# SCH_Line_Following_Robot_PCB_2023-12-15_.net
KiCad netlist of a schematic drawn in EasyEDA
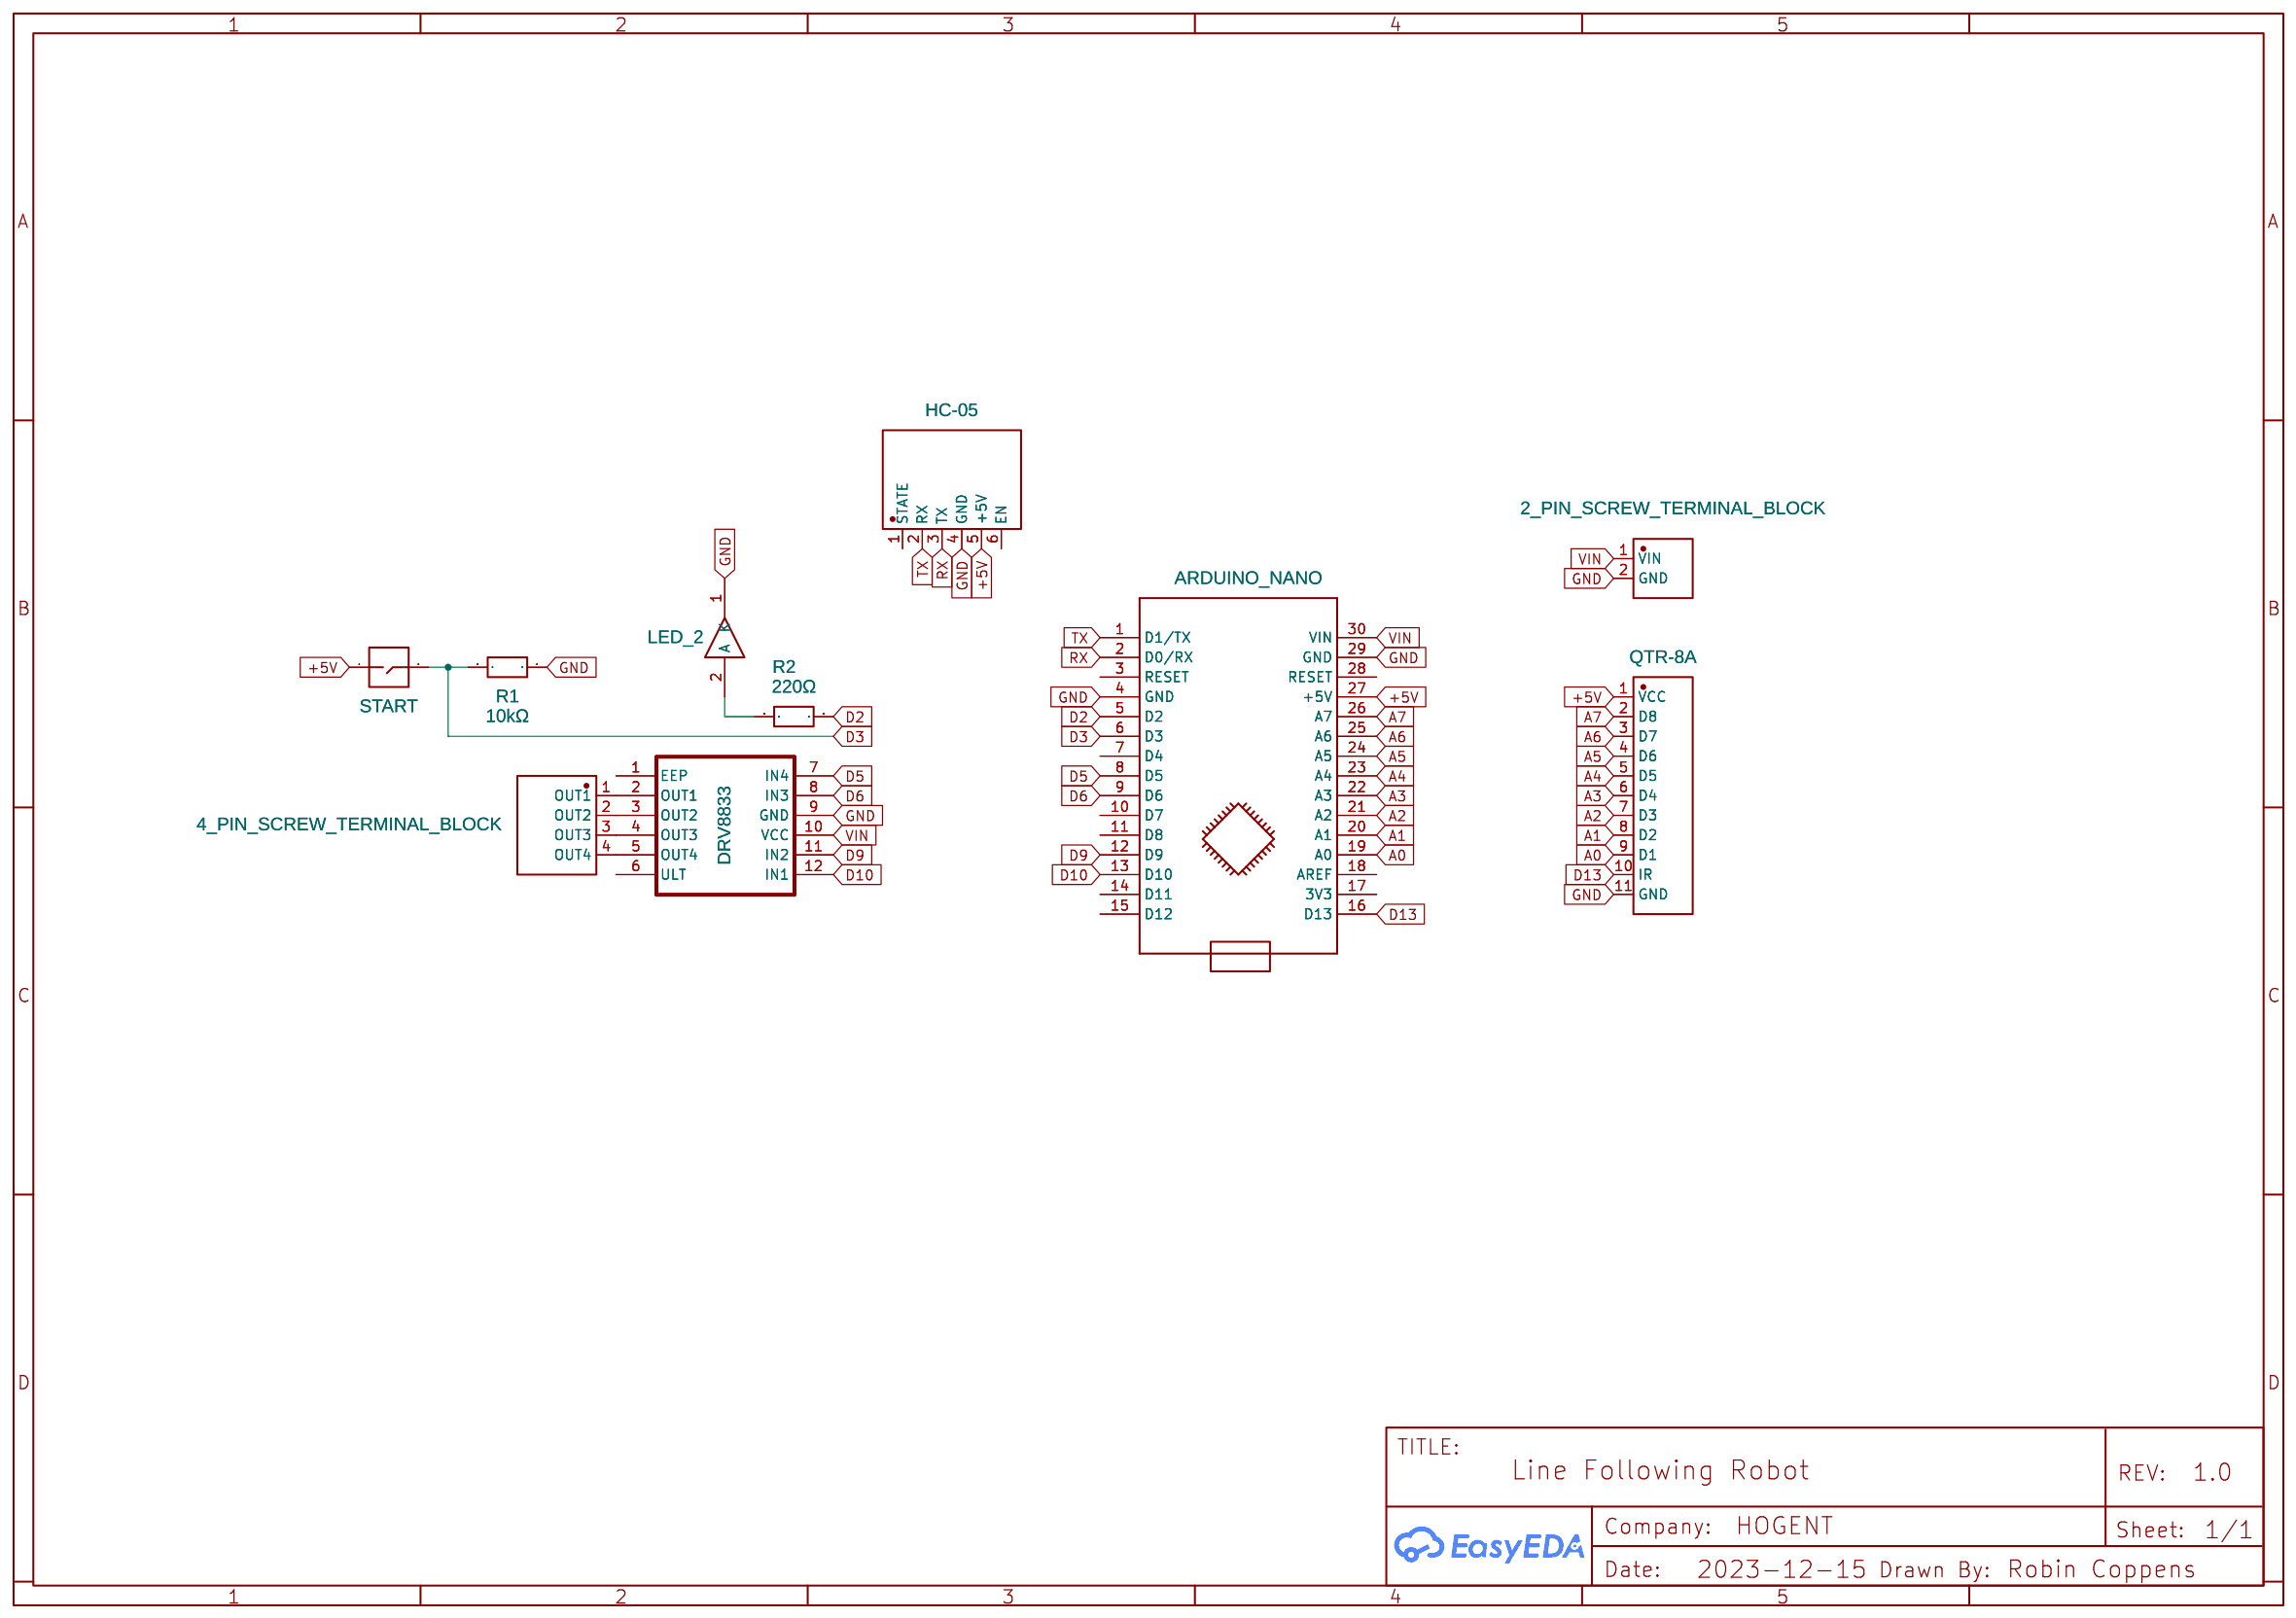
[diagram p0: schematic sheet]

(export (version "E")
  (design (tool "Eeschema 10.0.6"))
  (components
    (comp (ref "2_PIN_SCREW_TERMINAL_BLOCK")
      (value "2 Pin Screw Terminal Block Connector 2.54 mm")
      (libsource (lib "") (part "2 PIN SCREW TERMINAL BLOCK CONNECTOR 2.54 MM"))
    )
    (comp (ref "4_PIN_SCREW_TERMINAL_BLOCK")
      (value "4 PIN SCREW TERMINAL BLOCK CONNECTOR 2.54 MM")
      (libsource (lib "") (part "4 PIN SCREW TERMINAL BLOCK CONNECTOR 2.54 MM"))
    )
    (comp (ref "ARDUINO_NANO")
      (value "ARDUINO NANO CLOCK")
      (fields (field (name "Manufacturer Part") "Arduino-NANO"))
      (libsource (lib "") (part "ARDUINO NANO CLOCK"))
    )
    (comp (ref "DRV8833") (value "DRV8833") (libsource (lib "") (part "DRV8833 12PIN")))
    (comp (ref "HC-05") (value "HC-05") (libsource (lib "") (part "HC-05")))
    (comp (ref "LED_2") (value "led 5 mm") (libsource (lib "") (part "led 5 mm")))
    (comp (ref "QTR-8A") (value "QTR-8A") (libsource (lib "") (part "QTR-8A")))
    (comp (ref "R1")
      (value "10kΩ")
      (libsource (lib "") (part "AXIAL RESISTOR 220 OHM - TH_BD2.3-L6.0-P10.00-D0.4"))
    )
    (comp (ref "R2")
      (value "220Ω")
      (libsource (lib "") (part "AXIAL RESISTOR 220 OHM - TH_BD2.3-L6.0-P10.00-D0.4_1"))
    )
    (comp (ref "START") (value "start") (libsource (lib "") (part "Push Button")))
  )
  (nets
    (net (code "1") (name "+5V") (class "Default")
      (node (ref "ARDUINO_NANO") (pin "27") (pinfunction "+5V_27") (pintype "unspecified"))
      (node (ref "HC-05") (pin "5") (pinfunction "+5V_5") (pintype "unspecified"))
      (node (ref "QTR-8A") (pin "1") (pinfunction "VCC_1") (pintype "unspecified"))
      (node (ref "START") (pin "1") (pinfunction "1_1") (pintype "unspecified"))
    )
    (net (code "2") (name "A0") (class "Default")
      (node (ref "ARDUINO_NANO") (pin "19") (pinfunction "A0_19") (pintype "unspecified"))
      (node (ref "QTR-8A") (pin "9") (pinfunction "D1_9") (pintype "unspecified"))
    )
    (net (code "3") (name "A1") (class "Default")
      (node (ref "ARDUINO_NANO") (pin "20") (pinfunction "A1_20") (pintype "unspecified"))
      (node (ref "QTR-8A") (pin "8") (pinfunction "D2_8") (pintype "unspecified"))
    )
    (net (code "4") (name "A2") (class "Default")
      (node (ref "ARDUINO_NANO") (pin "21") (pinfunction "A2_21") (pintype "unspecified"))
      (node (ref "QTR-8A") (pin "7") (pinfunction "D3_7") (pintype "unspecified"))
    )
    (net (code "5") (name "A3") (class "Default")
      (node (ref "ARDUINO_NANO") (pin "22") (pinfunction "A3_22") (pintype "unspecified"))
      (node (ref "QTR-8A") (pin "6") (pinfunction "D4_6") (pintype "unspecified"))
    )
    (net (code "6") (name "A4") (class "Default")
      (node (ref "ARDUINO_NANO") (pin "23") (pinfunction "A4_23") (pintype "unspecified"))
      (node (ref "QTR-8A") (pin "5") (pinfunction "D5_5") (pintype "unspecified"))
    )
    (net (code "7") (name "A5") (class "Default")
      (node (ref "ARDUINO_NANO") (pin "24") (pinfunction "A5_24") (pintype "unspecified"))
      (node (ref "QTR-8A") (pin "4") (pinfunction "D6_4") (pintype "unspecified"))
    )
    (net (code "8") (name "A6") (class "Default")
      (node (ref "ARDUINO_NANO") (pin "25") (pinfunction "A6_25") (pintype "unspecified"))
      (node (ref "QTR-8A") (pin "3") (pinfunction "D7_3") (pintype "unspecified"))
    )
    (net (code "9") (name "A7") (class "Default")
      (node (ref "ARDUINO_NANO") (pin "26") (pinfunction "A7_26") (pintype "unspecified"))
      (node (ref "QTR-8A") (pin "2") (pinfunction "D8_2") (pintype "unspecified"))
    )
    (net (code "10") (name "D2") (class "Default")
      (node (ref "ARDUINO_NANO") (pin "5") (pinfunction "D2_5") (pintype "unspecified"))
      (node (ref "R2") (pin "2") (pinfunction "2_2") (pintype "unspecified"))
    )
    (net (code "11") (name "D3") (class "Default")
      (node (ref "ARDUINO_NANO") (pin "6") (pinfunction "D3_6") (pintype "unspecified"))
      (node (ref "R1") (pin "2") (pinfunction "2_2") (pintype "unspecified"))
      (node (ref "START") (pin "2") (pinfunction "2_2") (pintype "unspecified"))
    )
    (net (code "12") (name "D5") (class "Default")
      (node (ref "ARDUINO_NANO") (pin "8") (pinfunction "D5_8") (pintype "unspecified"))
      (node (ref "DRV8833") (pin "7") (pinfunction "IN4_7") (pintype "unspecified"))
    )
    (net (code "13") (name "D6") (class "Default")
      (node (ref "ARDUINO_NANO") (pin "9") (pinfunction "D6_9") (pintype "unspecified"))
      (node (ref "DRV8833") (pin "8") (pinfunction "IN3_8") (pintype "unspecified"))
    )
    (net (code "14") (name "D9") (class "Default")
      (node (ref "ARDUINO_NANO") (pin "12") (pinfunction "D9_12") (pintype "unspecified"))
      (node (ref "DRV8833") (pin "11") (pinfunction "IN2_11") (pintype "unspecified"))
    )
    (net (code "15") (name "D10") (class "Default")
      (node (ref "ARDUINO_NANO") (pin "13") (pinfunction "D10_13") (pintype "unspecified"))
      (node (ref "DRV8833") (pin "12") (pinfunction "IN1_12") (pintype "unspecified"))
    )
    (net (code "16") (name "D13") (class "Default")
      (node (ref "ARDUINO_NANO") (pin "16") (pinfunction "D13_16") (pintype "unspecified"))
      (node (ref "QTR-8A") (pin "10") (pinfunction "IR_10") (pintype "unspecified"))
    )
    (net (code "17") (name "GND") (class "Default")
      (node (ref "2_PIN_SCREW_TERMINAL_BLOCK") (pin "2") (pinfunction "GND_2") (pintype "unspecified"))
      (node (ref "ARDUINO_NANO") (pin "29") (pinfunction "GND_29") (pintype "unspecified"))
      (node (ref "ARDUINO_NANO") (pin "4") (pinfunction "GND_4") (pintype "unspecified"))
      (node (ref "DRV8833") (pin "9") (pinfunction "GND_9") (pintype "unspecified"))
      (node (ref "HC-05") (pin "4") (pinfunction "GND_4") (pintype "unspecified"))
      (node (ref "LED_2") (pin "1") (pinfunction "K_1") (pintype "unspecified"))
      (node (ref "QTR-8A") (pin "11") (pinfunction "GND_11") (pintype "unspecified"))
      (node (ref "R1") (pin "1") (pinfunction "1_1") (pintype "unspecified"))
    )
    (net (code "18") (name "Net-(4_PIN_SCREW_TERMINAL_BLOCK-OUT1)") (class "Default")
      (node (ref "4_PIN_SCREW_TERMINAL_BLOCK") (pin "1") (pinfunction "OUT1_1") (pintype "unspecified"))
      (node (ref "DRV8833") (pin "2") (pinfunction "OUT1_2") (pintype "unspecified"))
    )
    (net (code "19") (name "Net-(4_PIN_SCREW_TERMINAL_BLOCK-OUT2)") (class "Default")
      (node (ref "4_PIN_SCREW_TERMINAL_BLOCK") (pin "2") (pinfunction "OUT2_2") (pintype "unspecified"))
      (node (ref "DRV8833") (pin "3") (pinfunction "OUT2_3") (pintype "unspecified"))
    )
    (net (code "20") (name "Net-(4_PIN_SCREW_TERMINAL_BLOCK-OUT3)") (class "Default")
      (node (ref "4_PIN_SCREW_TERMINAL_BLOCK") (pin "3") (pinfunction "OUT3_3") (pintype "unspecified"))
      (node (ref "DRV8833") (pin "4") (pinfunction "OUT3_4") (pintype "unspecified"))
    )
    (net (code "21") (name "Net-(4_PIN_SCREW_TERMINAL_BLOCK-OUT4)") (class "Default")
      (node (ref "4_PIN_SCREW_TERMINAL_BLOCK") (pin "4") (pinfunction "OUT4_4") (pintype "unspecified"))
      (node (ref "DRV8833") (pin "5") (pinfunction "OUT4_5") (pintype "unspecified"))
    )
    (net (code "22") (name "Net-(LED_2-A)") (class "Default")
      (node (ref "LED_2") (pin "2") (pinfunction "A_2") (pintype "unspecified"))
      (node (ref "R2") (pin "1") (pinfunction "1_1") (pintype "unspecified"))
    )
    (net (code "23") (name "RX") (class "Default")
      (node (ref "ARDUINO_NANO") (pin "2") (pinfunction "D0/RX_2") (pintype "unspecified"))
      (node (ref "HC-05") (pin "3") (pinfunction "TX_3") (pintype "unspecified"))
    )
    (net (code "24") (name "TX") (class "Default")
      (node (ref "ARDUINO_NANO") (pin "1") (pinfunction "D1/TX_1") (pintype "unspecified"))
      (node (ref "HC-05") (pin "2") (pinfunction "RX_2") (pintype "unspecified"))
    )
    (net (code "25") (name "VIN") (class "Default")
      (node (ref "2_PIN_SCREW_TERMINAL_BLOCK") (pin "1") (pinfunction "VIN_1") (pintype "unspecified"))
      (node (ref "ARDUINO_NANO") (pin "30") (pinfunction "VIN_30") (pintype "unspecified"))
      (node (ref "DRV8833") (pin "10") (pinfunction "VCC_10") (pintype "unspecified"))
    )
    (net (code "26") (name "unconnected-(ARDUINO_NANO-3V3-Pad17)") (class "Default")
      (node (ref "ARDUINO_NANO") (pin "17") (pinfunction "3V3_17") (pintype "unspecified"))
    )
    (net (code "27") (name "unconnected-(ARDUINO_NANO-AREF-Pad18)") (class "Default")
      (node (ref "ARDUINO_NANO") (pin "18") (pinfunction "AREF_18") (pintype "unspecified"))
    )
    (net (code "28") (name "unconnected-(ARDUINO_NANO-D4-Pad7)") (class "Default")
      (node (ref "ARDUINO_NANO") (pin "7") (pinfunction "D4_7") (pintype "unspecified"))
    )
    (net (code "29") (name "unconnected-(ARDUINO_NANO-D7-Pad10)") (class "Default")
      (node (ref "ARDUINO_NANO") (pin "10") (pinfunction "D7_10") (pintype "unspecified"))
    )
    (net (code "30") (name "unconnected-(ARDUINO_NANO-D8-Pad11)") (class "Default")
      (node (ref "ARDUINO_NANO") (pin "11") (pinfunction "D8_11") (pintype "unspecified"))
    )
    (net (code "31") (name "unconnected-(ARDUINO_NANO-D11-Pad14)") (class "Default")
      (node (ref "ARDUINO_NANO") (pin "14") (pinfunction "D11_14") (pintype "unspecified"))
    )
    (net (code "32") (name "unconnected-(ARDUINO_NANO-D12-Pad15)") (class "Default")
      (node (ref "ARDUINO_NANO") (pin "15") (pinfunction "D12_15") (pintype "unspecified"))
    )
    (net (code "33") (name "unconnected-(ARDUINO_NANO-RESET-Pad3)") (class "Default")
      (node (ref "ARDUINO_NANO") (pin "3") (pinfunction "RESET_3") (pintype "unspecified"))
    )
    (net (code "34") (name "unconnected-(ARDUINO_NANO-RESET-Pad28)") (class "Default")
      (node (ref "ARDUINO_NANO") (pin "28") (pinfunction "RESET_28") (pintype "unspecified"))
    )
    (net (code "35") (name "unconnected-(DRV8833-EEP-Pad1)") (class "Default")
      (node (ref "DRV8833") (pin "1") (pinfunction "EEP_1") (pintype "unspecified"))
    )
    (net (code "36") (name "unconnected-(DRV8833-ULT-Pad6)") (class "Default")
      (node (ref "DRV8833") (pin "6") (pinfunction "ULT_6") (pintype "unspecified"))
    )
    (net (code "37") (name "unconnected-(HC-05-EN-Pad6)") (class "Default")
      (node (ref "HC-05") (pin "6") (pinfunction "EN_6") (pintype "unspecified"))
    )
    (net (code "38") (name "unconnected-(HC-05-STATE-Pad1)") (class "Default")
      (node (ref "HC-05") (pin "1") (pinfunction "STATE_1") (pintype "unspecified"))
    )
  )
)
